# zero_board.net
KiCad netlist of a schematic drawn in EAGLE
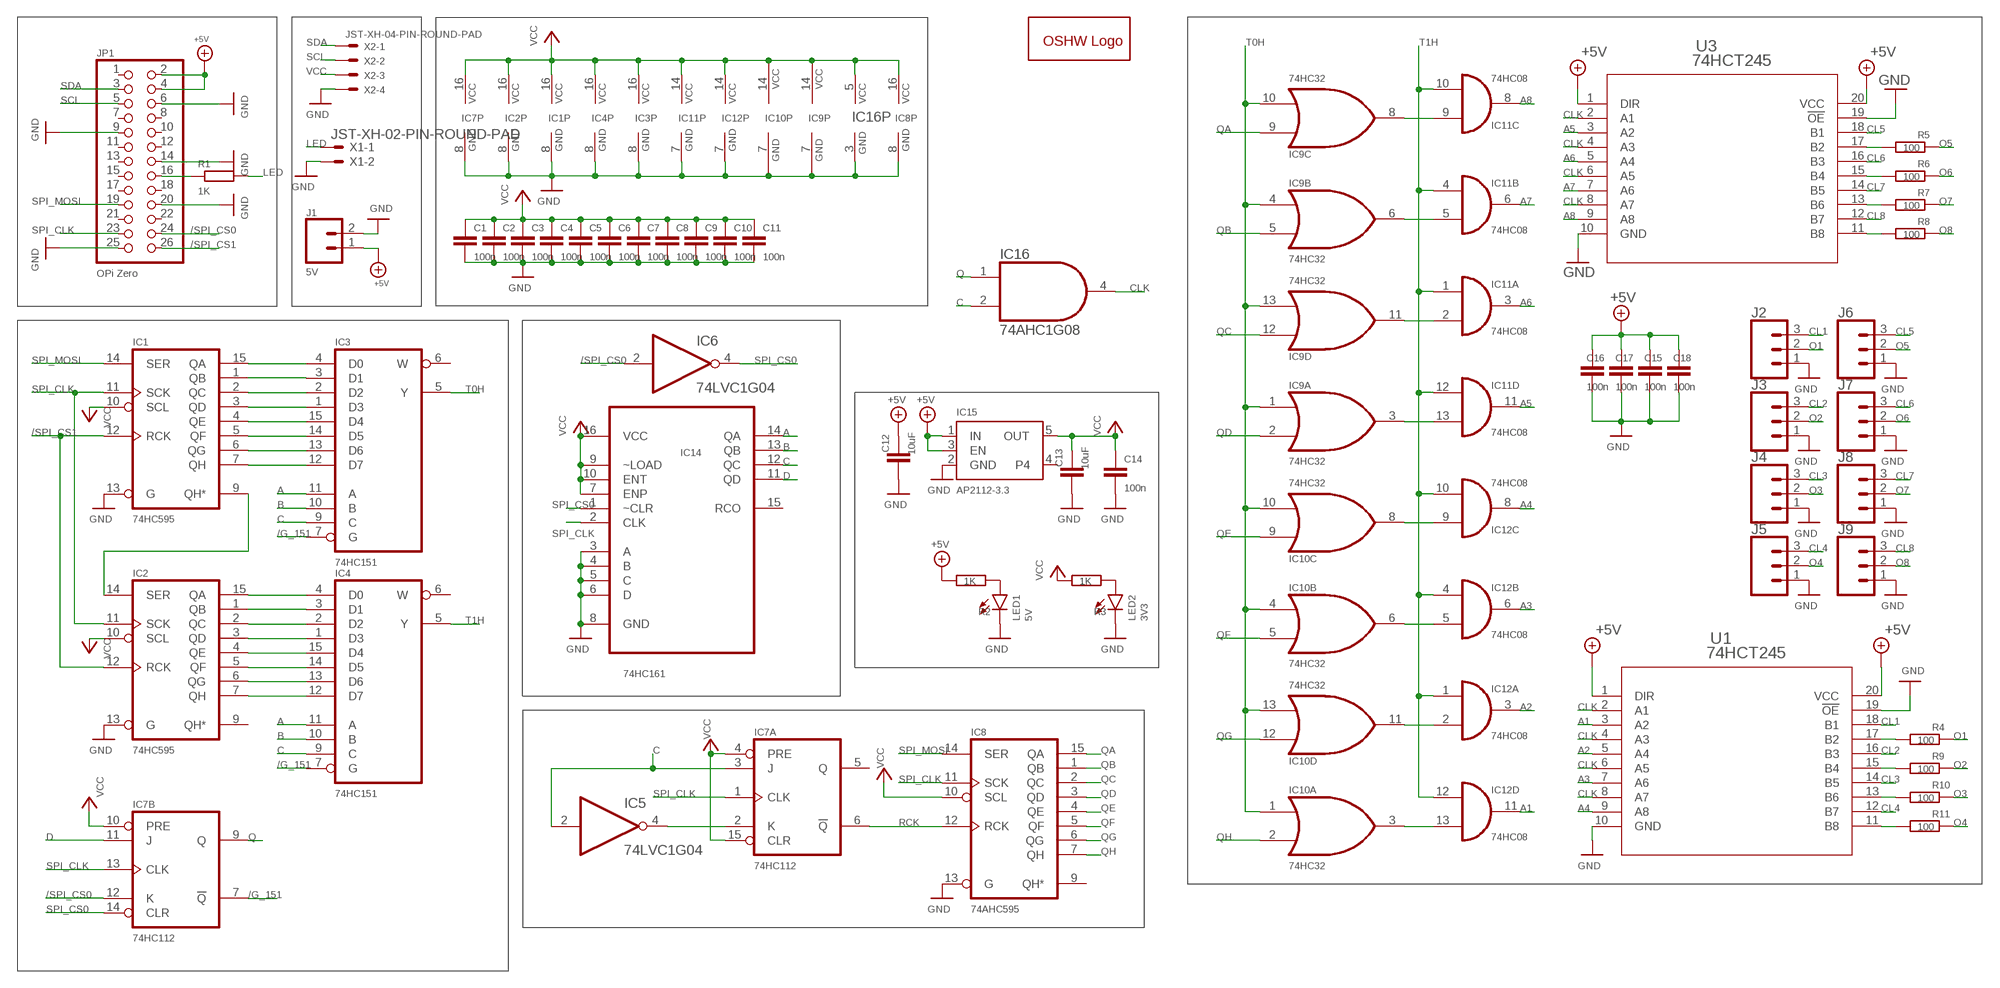
[diagram p0: schematic, sheet 1]

(export (version "E")
  (design (tool "Eeschema 10.0.6"))
  (components
    (comp (ref "C1")
      (value "100n")
      (footprint "eagle-import:C0603")
      (libsource (lib "eagle-import") (part "C-EUC0603"))
    )
    (comp (ref "C2")
      (value "100n")
      (footprint "eagle-import:C0603")
      (libsource (lib "eagle-import") (part "C-EUC0603"))
    )
    (comp (ref "C3")
      (value "100n")
      (footprint "eagle-import:C0603")
      (libsource (lib "eagle-import") (part "C-EUC0603"))
    )
    (comp (ref "C4")
      (value "100n")
      (footprint "eagle-import:C0603")
      (libsource (lib "eagle-import") (part "C-EUC0603"))
    )
    (comp (ref "C5")
      (value "100n")
      (footprint "eagle-import:C0603")
      (libsource (lib "eagle-import") (part "C-EUC0603"))
    )
    (comp (ref "C6")
      (value "100n")
      (footprint "eagle-import:C0603")
      (libsource (lib "eagle-import") (part "C-EUC0603"))
    )
    (comp (ref "C7")
      (value "100n")
      (footprint "eagle-import:C0603")
      (libsource (lib "eagle-import") (part "C-EUC0603"))
    )
    (comp (ref "C8")
      (value "100n")
      (footprint "eagle-import:C0603")
      (libsource (lib "eagle-import") (part "C-EUC0603"))
    )
    (comp (ref "C9")
      (value "100n")
      (footprint "eagle-import:C0603")
      (libsource (lib "eagle-import") (part "C-EUC0603"))
    )
    (comp (ref "C10")
      (value "100n")
      (footprint "eagle-import:C0603")
      (libsource (lib "eagle-import") (part "C-EUC0603"))
    )
    (comp (ref "C11")
      (value "100n")
      (footprint "eagle-import:C0603")
      (libsource (lib "eagle-import") (part "C-EUC0603"))
    )
    (comp (ref "C12")
      (value "10uF")
      (footprint "eagle-import:C0805")
      (libsource (lib "eagle-import") (part "C-EUC0805"))
    )
    (comp (ref "C13")
      (value "10uF")
      (footprint "eagle-import:C0805")
      (libsource (lib "eagle-import") (part "C-EUC0805"))
    )
    (comp (ref "C14")
      (value "100n")
      (footprint "eagle-import:C0603")
      (libsource (lib "eagle-import") (part "C-EUC0603"))
    )
    (comp (ref "C15")
      (value "100n")
      (footprint "eagle-import:C0603")
      (libsource (lib "eagle-import") (part "C-EUC0603"))
    )
    (comp (ref "C16")
      (value "100n")
      (footprint "eagle-import:C0603")
      (libsource (lib "eagle-import") (part "C-EUC0603"))
    )
    (comp (ref "C17")
      (value "100n")
      (footprint "eagle-import:C0603")
      (libsource (lib "eagle-import") (part "C-EUC0603"))
    )
    (comp (ref "C18")
      (value "100n")
      (footprint "eagle-import:C0603")
      (libsource (lib "eagle-import") (part "C-EUC0603"))
    )
    (comp (ref "GOLD_ORB_SM1")
      (value "OSHWLOGOLOGO5MM")
      (footprint "eagle-import:OSHW_5MM")
      (libsource (lib "eagle-import") (part "OSHWLOGOLOGO5MM"))
    )
    (comp (ref "IC1")
      (value "74HC595")
      (footprint "eagle-import:SO16")
      (libsource (lib "eagle-import") (part "74595DHC"))
    )
    (comp (ref "IC2")
      (value "74HC595")
      (footprint "eagle-import:SO16")
      (libsource (lib "eagle-import") (part "74595DHC"))
    )
    (comp (ref "IC3")
      (value "74HC151")
      (footprint "eagle-import:SO16")
      (libsource (lib "eagle-import") (part "74151DHC"))
    )
    (comp (ref "IC4")
      (value "74HC151")
      (footprint "eagle-import:SO16")
      (libsource (lib "eagle-import") (part "74151DHC"))
    )
    (comp (ref "IC5")
      (value "74LVC1G04")
      (footprint "eagle-import:SC70-5")
      (libsource (lib "eagle-import") (part "741G04DCKLVC"))
    )
    (comp (ref "IC6")
      (value "74LVC1G04")
      (footprint "eagle-import:SC70-5")
      (libsource (lib "eagle-import") (part "741G04DCKLVC"))
    )
    (comp (ref "IC7")
      (value "74HC112")
      (footprint "eagle-import:SO16")
      (libsource (lib "eagle-import") (part "74112DHC"))
    )
    (comp (ref "IC8")
      (value "74AHC595")
      (footprint "eagle-import:SO16")
      (libsource (lib "eagle-import") (part "74595DHC"))
    )
    (comp (ref "IC9")
      (value "74HC32")
      (footprint "eagle-import:SO14")
      (libsource (lib "eagle-import") (part "7432DLS"))
    )
    (comp (ref "IC10")
      (value "74HC32")
      (footprint "eagle-import:SO14")
      (libsource (lib "eagle-import") (part "7432DLS"))
    )
    (comp (ref "IC11")
      (value "74HC08")
      (footprint "eagle-import:SO14")
      (libsource (lib "eagle-import") (part "7408DHC"))
    )
    (comp (ref "IC12")
      (value "74HC08")
      (footprint "eagle-import:SO14")
      (libsource (lib "eagle-import") (part "7408DHC"))
    )
    (comp (ref "IC14")
      (value "74HC161")
      (footprint "eagle-import:SOIC127P600X175-16N")
      (fields (field (name "MF") "Texas Instruments") (field (name "MP") "SN74HC161DR"))
      (libsource (lib "eagle-import") (part "SN74HC161DR"))
    )
    (comp (ref "IC15")
      (value "AP2112-3.3")
      (footprint "eagle-import:SOT23-5")
      (libsource (lib "eagle-import") (part "VREG_SOT23-5"))
    )
    (comp (ref "IC16")
      (value "74AHC1G08")
      (footprint "eagle-import:SC70-5")
      (libsource (lib "eagle-import") (part "741G08DCKAHC"))
    )
    (comp (ref "J1")
      (value "5V")
      (footprint "eagle-import:SCREWTERMINAL-3.5MM-2")
      (libsource (lib "eagle-import") (part "CONN_023.5MM"))
    )
    (comp (ref "J2")
      (value "CONN_03SCREW-NS")
      (footprint "eagle-import:SCREWTERMINAL-3.5MM-3-NS")
      (libsource (lib "eagle-import") (part "CONN_03SCREW-NS"))
    )
    (comp (ref "J3")
      (value "CONN_03SCREW-NS")
      (footprint "eagle-import:SCREWTERMINAL-3.5MM-3-NS")
      (libsource (lib "eagle-import") (part "CONN_03SCREW-NS"))
    )
    (comp (ref "J4")
      (value "CONN_03SCREW-NS")
      (footprint "eagle-import:SCREWTERMINAL-3.5MM-3-NS")
      (libsource (lib "eagle-import") (part "CONN_03SCREW-NS"))
    )
    (comp (ref "J5")
      (value "CONN_03SCREW-NS")
      (footprint "eagle-import:SCREWTERMINAL-3.5MM-3-NS")
      (libsource (lib "eagle-import") (part "CONN_03SCREW-NS"))
    )
    (comp (ref "J6")
      (value "CONN_03SCREW-NS")
      (footprint "eagle-import:SCREWTERMINAL-3.5MM-3-NS")
      (libsource (lib "eagle-import") (part "CONN_03SCREW-NS"))
    )
    (comp (ref "J7")
      (value "CONN_03SCREW-NS")
      (footprint "eagle-import:SCREWTERMINAL-3.5MM-3-NS")
      (libsource (lib "eagle-import") (part "CONN_03SCREW-NS"))
    )
    (comp (ref "J8")
      (value "CONN_03SCREW-NS")
      (footprint "eagle-import:SCREWTERMINAL-3.5MM-3-NS")
      (libsource (lib "eagle-import") (part "CONN_03SCREW-NS"))
    )
    (comp (ref "J9")
      (value "CONN_03SCREW-NS")
      (footprint "eagle-import:SCREWTERMINAL-3.5MM-3-NS")
      (libsource (lib "eagle-import") (part "CONN_03SCREW-NS"))
    )
    (comp (ref "JP1")
      (value "OPi Zero")
      (footprint "eagle-import:2X13")
      (libsource (lib "eagle-import") (part "PINHD-2X13"))
    )
    (comp (ref "LED1")
      (value "5V")
      (footprint "eagle-import:CHIP-LED0603")
      (libsource (lib "eagle-import") (part "LEDCHIP-LED0603"))
    )
    (comp (ref "LED2")
      (value "3V3")
      (footprint "eagle-import:CHIP-LED0603")
      (libsource (lib "eagle-import") (part "LEDCHIP-LED0603"))
    )
    (comp (ref "R1")
      (value "1K")
      (footprint "eagle-import:R0603")
      (libsource (lib "eagle-import") (part "R-EU_R0603"))
    )
    (comp (ref "R2")
      (value "1K")
      (footprint "eagle-import:R0603")
      (libsource (lib "eagle-import") (part "R-EU_R0603"))
    )
    (comp (ref "R3")
      (value "1K")
      (footprint "eagle-import:R0603")
      (libsource (lib "eagle-import") (part "R-EU_R0603"))
    )
    (comp (ref "R4")
      (value "100")
      (footprint "eagle-import:R0603")
      (libsource (lib "eagle-import") (part "R-EU_R0603"))
    )
    (comp (ref "R5")
      (value "100")
      (footprint "eagle-import:R0603")
      (libsource (lib "eagle-import") (part "R-EU_R0603"))
    )
    (comp (ref "R6")
      (value "100")
      (footprint "eagle-import:R0603")
      (libsource (lib "eagle-import") (part "R-EU_R0603"))
    )
    (comp (ref "R7")
      (value "100")
      (footprint "eagle-import:R0603")
      (libsource (lib "eagle-import") (part "R-EU_R0603"))
    )
    (comp (ref "R8")
      (value "100")
      (footprint "eagle-import:R0603")
      (libsource (lib "eagle-import") (part "R-EU_R0603"))
    )
    (comp (ref "R9")
      (value "100")
      (footprint "eagle-import:R0603")
      (libsource (lib "eagle-import") (part "R-EU_R0603"))
    )
    (comp (ref "R10")
      (value "100")
      (footprint "eagle-import:R0603")
      (libsource (lib "eagle-import") (part "R-EU_R0603"))
    )
    (comp (ref "R11")
      (value "100")
      (footprint "eagle-import:R0603")
      (libsource (lib "eagle-import") (part "R-EU_R0603"))
    )
    (comp (ref "U1")
      (value "74HCT245")
      (footprint "eagle-import:PW20")
      (fields
        (field (name "GENERIC_PART_NUMBER") "SN74HCT245")
        (field (name "MANUFACTURER") "Texas Instruments")
        (field (name "MANUFACTURER_PART_NUMBER") "SN74HCT245PWR")
      )
      (libsource (lib "eagle-import") (part "SN74HCT245PWR"))
    )
    (comp (ref "U3")
      (value "74HCT245")
      (footprint "eagle-import:PW20")
      (fields
        (field (name "GENERIC_PART_NUMBER") "SN74HCT245")
        (field (name "MANUFACTURER") "Texas Instruments")
        (field (name "MANUFACTURER_PART_NUMBER") "SN74HCT245PWR")
      )
      (libsource (lib "eagle-import") (part "SN74HCT245PWR"))
    )
    (comp (ref "X1")
      (value "JST-XH-02-PIN-ROUND-PAD")
      (footprint "eagle-import:JST-XH-02-PACKAGE-ROUND-PAD")
      (libsource (lib "eagle-import") (part "JST-XH-02-PIN-ROUND-PAD"))
    )
    (comp (ref "X2")
      (value "JST-XH-04-PIN-ROUND-PAD")
      (footprint "eagle-import:JST-XH-04-PACKAGE-ROUND-PAD")
      (libsource (lib "eagle-import") (part "JST-XH-04-PIN-ROUND-PAD"))
    )
  )
  (nets
    (net (code "1") (name "+5V") (class "Default")
      (node (ref "C12") (pin "1") (pinfunction "1_1") (pintype "passive"))
      (node (ref "C15") (pin "1") (pinfunction "1_1") (pintype "passive"))
      (node (ref "C16") (pin "1") (pinfunction "1_1") (pintype "passive"))
      (node (ref "C17") (pin "1") (pinfunction "1_1") (pintype "passive"))
      (node (ref "C18") (pin "1") (pinfunction "1_1") (pintype "passive"))
      (node (ref "IC15") (pin "1") (pinfunction "IN_1") (pintype "power_in"))
      (node (ref "IC15") (pin "3") (pinfunction "EN_3") (pintype "input"))
      (node (ref "J1") (pin "1") (pinfunction "1_1") (pintype "passive"))
      (node (ref "JP1") (pin "2") (pinfunction "2_2") (pintype "passive"))
      (node (ref "JP1") (pin "4") (pinfunction "4_4") (pintype "passive"))
      (node (ref "R2") (pin "1") (pinfunction "1_1") (pintype "passive"))
      (node (ref "U1") (pin "1") (pinfunction "DIR_1") (pintype "input"))
      (node (ref "U1") (pin "20") (pinfunction "VCC_20") (pintype "power_in"))
      (node (ref "U3") (pin "1") (pinfunction "DIR_1") (pintype "input"))
      (node (ref "U3") (pin "20") (pinfunction "VCC_20") (pintype "power_in"))
    )
    (net (code "2") (name "/A") (class "Default")
      (node (ref "IC14") (pin "14") (pinfunction "QA_14") (pintype "output"))
      (node (ref "IC3") (pin "11") (pinfunction "A_11") (pintype "input"))
      (node (ref "IC4") (pin "11") (pinfunction "A_11") (pintype "input"))
    )
    (net (code "3") (name "/A1") (class "Default")
      (node (ref "IC12") (pin "11") (pinfunction "O_11") (pintype "output"))
      (node (ref "U1") (pin "3") (pinfunction "A2_3") (pintype "bidirectional"))
    )
    (net (code "4") (name "/A2") (class "Default")
      (node (ref "IC12") (pin "3") (pinfunction "O_3") (pintype "output"))
      (node (ref "U1") (pin "5") (pinfunction "A4_5") (pintype "bidirectional"))
    )
    (net (code "5") (name "/A3") (class "Default")
      (node (ref "IC12") (pin "6") (pinfunction "O_6") (pintype "output"))
      (node (ref "U1") (pin "7") (pinfunction "A6_7") (pintype "bidirectional"))
    )
    (net (code "6") (name "/A4") (class "Default")
      (node (ref "IC12") (pin "8") (pinfunction "O_8") (pintype "output"))
      (node (ref "U1") (pin "9") (pinfunction "A8_9") (pintype "bidirectional"))
    )
    (net (code "7") (name "/A5") (class "Default")
      (node (ref "IC11") (pin "11") (pinfunction "O_11") (pintype "output"))
      (node (ref "U3") (pin "3") (pinfunction "A2_3") (pintype "bidirectional"))
    )
    (net (code "8") (name "/A6") (class "Default")
      (node (ref "IC11") (pin "3") (pinfunction "O_3") (pintype "output"))
      (node (ref "U3") (pin "5") (pinfunction "A4_5") (pintype "bidirectional"))
    )
    (net (code "9") (name "/A7") (class "Default")
      (node (ref "IC11") (pin "6") (pinfunction "O_6") (pintype "output"))
      (node (ref "U3") (pin "7") (pinfunction "A6_7") (pintype "bidirectional"))
    )
    (net (code "10") (name "/A8") (class "Default")
      (node (ref "IC11") (pin "8") (pinfunction "O_8") (pintype "output"))
      (node (ref "U3") (pin "9") (pinfunction "A8_9") (pintype "bidirectional"))
    )
    (net (code "11") (name "/B") (class "Default")
      (node (ref "IC14") (pin "13") (pinfunction "QB_13") (pintype "output"))
      (node (ref "IC3") (pin "10") (pinfunction "B_10") (pintype "input"))
      (node (ref "IC4") (pin "10") (pinfunction "B_10") (pintype "input"))
    )
    (net (code "12") (name "/C") (class "Default")
      (node (ref "IC14") (pin "12") (pinfunction "QC_12") (pintype "output"))
      (node (ref "IC16") (pin "2") (pinfunction "I1_2") (pintype "input"))
      (node (ref "IC3") (pin "9") (pinfunction "C_9") (pintype "input"))
      (node (ref "IC4") (pin "9") (pinfunction "C_9") (pintype "input"))
      (node (ref "IC5") (pin "2") (pinfunction "I_2") (pintype "input"))
      (node (ref "IC7") (pin "3") (pinfunction "J_3") (pintype "input"))
    )
    (net (code "13") (name "/CL1") (class "Default")
      (node (ref "J2") (pin "3") (pinfunction "3_3") (pintype "passive"))
      (node (ref "U1") (pin "18") (pinfunction "B1_18") (pintype "bidirectional"))
    )
    (net (code "14") (name "/CL2") (class "Default")
      (node (ref "J3") (pin "3") (pinfunction "3_3") (pintype "passive"))
      (node (ref "U1") (pin "16") (pinfunction "B3_16") (pintype "bidirectional"))
    )
    (net (code "15") (name "/CL3") (class "Default")
      (node (ref "J4") (pin "3") (pinfunction "3_3") (pintype "passive"))
      (node (ref "U1") (pin "14") (pinfunction "B5_14") (pintype "bidirectional"))
    )
    (net (code "16") (name "/CL4") (class "Default")
      (node (ref "J5") (pin "3") (pinfunction "3_3") (pintype "passive"))
      (node (ref "U1") (pin "12") (pinfunction "B7_12") (pintype "bidirectional"))
    )
    (net (code "17") (name "/CL5") (class "Default")
      (node (ref "J6") (pin "3") (pinfunction "3_3") (pintype "passive"))
      (node (ref "U3") (pin "18") (pinfunction "B1_18") (pintype "bidirectional"))
    )
    (net (code "18") (name "/CL6") (class "Default")
      (node (ref "J7") (pin "3") (pinfunction "3_3") (pintype "passive"))
      (node (ref "U3") (pin "16") (pinfunction "B3_16") (pintype "bidirectional"))
    )
    (net (code "19") (name "/CL7") (class "Default")
      (node (ref "J8") (pin "3") (pinfunction "3_3") (pintype "passive"))
      (node (ref "U3") (pin "14") (pinfunction "B5_14") (pintype "bidirectional"))
    )
    (net (code "20") (name "/CL8") (class "Default")
      (node (ref "J9") (pin "3") (pinfunction "3_3") (pintype "passive"))
      (node (ref "U3") (pin "12") (pinfunction "B7_12") (pintype "bidirectional"))
    )
    (net (code "21") (name "/CLK") (class "Default")
      (node (ref "IC16") (pin "4") (pinfunction "O_4") (pintype "output"))
      (node (ref "U1") (pin "2") (pinfunction "A1_2") (pintype "bidirectional"))
      (node (ref "U1") (pin "4") (pinfunction "A3_4") (pintype "bidirectional"))
      (node (ref "U1") (pin "6") (pinfunction "A5_6") (pintype "bidirectional"))
      (node (ref "U1") (pin "8") (pinfunction "A7_8") (pintype "bidirectional"))
      (node (ref "U3") (pin "2") (pinfunction "A1_2") (pintype "bidirectional"))
      (node (ref "U3") (pin "4") (pinfunction "A3_4") (pintype "bidirectional"))
      (node (ref "U3") (pin "6") (pinfunction "A5_6") (pintype "bidirectional"))
      (node (ref "U3") (pin "8") (pinfunction "A7_8") (pintype "bidirectional"))
    )
    (net (code "22") (name "/D") (class "Default")
      (node (ref "IC14") (pin "11") (pinfunction "QD_11") (pintype "output"))
      (node (ref "IC7") (pin "11") (pinfunction "J_11") (pintype "input"))
    )
    (net (code "23") (name "/LED") (class "Default")
      (node (ref "R1") (pin "2") (pinfunction "2_2") (pintype "passive"))
      (node (ref "X1") (pin "1") (pinfunction "S_1") (pintype "passive"))
    )
    (net (code "24") (name "/O1") (class "Default")
      (node (ref "J2") (pin "2") (pinfunction "2_2") (pintype "passive"))
      (node (ref "R4") (pin "2") (pinfunction "2_2") (pintype "passive"))
    )
    (net (code "25") (name "/O2") (class "Default")
      (node (ref "J3") (pin "2") (pinfunction "2_2") (pintype "passive"))
      (node (ref "R9") (pin "2") (pinfunction "2_2") (pintype "passive"))
    )
    (net (code "26") (name "/O3") (class "Default")
      (node (ref "J4") (pin "2") (pinfunction "2_2") (pintype "passive"))
      (node (ref "R10") (pin "2") (pinfunction "2_2") (pintype "passive"))
    )
    (net (code "27") (name "/O4") (class "Default")
      (node (ref "J5") (pin "2") (pinfunction "2_2") (pintype "passive"))
      (node (ref "R11") (pin "2") (pinfunction "2_2") (pintype "passive"))
    )
    (net (code "28") (name "/O5") (class "Default")
      (node (ref "J6") (pin "2") (pinfunction "2_2") (pintype "passive"))
      (node (ref "R5") (pin "2") (pinfunction "2_2") (pintype "passive"))
    )
    (net (code "29") (name "/O6") (class "Default")
      (node (ref "J7") (pin "2") (pinfunction "2_2") (pintype "passive"))
      (node (ref "R6") (pin "2") (pinfunction "2_2") (pintype "passive"))
    )
    (net (code "30") (name "/O7") (class "Default")
      (node (ref "J8") (pin "2") (pinfunction "2_2") (pintype "passive"))
      (node (ref "R7") (pin "2") (pinfunction "2_2") (pintype "passive"))
    )
    (net (code "31") (name "/O8") (class "Default")
      (node (ref "J9") (pin "2") (pinfunction "2_2") (pintype "passive"))
      (node (ref "R8") (pin "2") (pinfunction "2_2") (pintype "passive"))
    )
    (net (code "32") (name "/Q") (class "Default")
      (node (ref "IC16") (pin "1") (pinfunction "I0_1") (pintype "input"))
      (node (ref "IC7") (pin "9") (pinfunction "Q_9") (pintype "output"))
    )
    (net (code "33") (name "/QA") (class "Default")
      (node (ref "IC8") (pin "15") (pinfunction "QA_15") (pintype "tri_state"))
      (node (ref "IC9") (pin "9") (pinfunction "I0_9") (pintype "input"))
    )
    (net (code "34") (name "/QB") (class "Default")
      (node (ref "IC8") (pin "1") (pinfunction "QB_1") (pintype "tri_state"))
      (node (ref "IC9") (pin "5") (pinfunction "I1_5") (pintype "input"))
    )
    (net (code "35") (name "/QC") (class "Default")
      (node (ref "IC8") (pin "2") (pinfunction "QC_2") (pintype "tri_state"))
      (node (ref "IC9") (pin "12") (pinfunction "I0_12") (pintype "input"))
    )
    (net (code "36") (name "/QD") (class "Default")
      (node (ref "IC8") (pin "3") (pinfunction "QD_3") (pintype "tri_state"))
      (node (ref "IC9") (pin "2") (pinfunction "I1_2") (pintype "input"))
    )
    (net (code "37") (name "/QE") (class "Default")
      (node (ref "IC10") (pin "9") (pinfunction "I0_9") (pintype "input"))
      (node (ref "IC8") (pin "4") (pinfunction "QE_4") (pintype "tri_state"))
    )
    (net (code "38") (name "/QF") (class "Default")
      (node (ref "IC10") (pin "5") (pinfunction "I1_5") (pintype "input"))
      (node (ref "IC8") (pin "5") (pinfunction "QF_5") (pintype "tri_state"))
    )
    (net (code "39") (name "/QG") (class "Default")
      (node (ref "IC10") (pin "12") (pinfunction "I0_12") (pintype "input"))
      (node (ref "IC8") (pin "6") (pinfunction "QG_6") (pintype "tri_state"))
    )
    (net (code "40") (name "/QH") (class "Default")
      (node (ref "IC10") (pin "2") (pinfunction "I1_2") (pintype "input"))
      (node (ref "IC8") (pin "7") (pinfunction "QH_7") (pintype "tri_state"))
    )
    (net (code "41") (name "/RCK") (class "Default")
      (node (ref "IC7") (pin "6") (pinfunction "~{Q}_6") (pintype "output"))
      (node (ref "IC8") (pin "12") (pinfunction "RCK_12") (pintype "input"))
    )
    (net (code "42") (name "/SCL") (class "Default")
      (node (ref "JP1") (pin "5") (pinfunction "5_5") (pintype "passive"))
      (node (ref "X2") (pin "2") (pinfunction "S_2") (pintype "passive"))
    )
    (net (code "43") (name "/SDA") (class "Default")
      (node (ref "JP1") (pin "3") (pinfunction "3_3") (pintype "passive"))
      (node (ref "X2") (pin "1") (pinfunction "S_1") (pintype "passive"))
    )
    (net (code "44") (name "/SPI_CLK") (class "Default")
      (node (ref "IC1") (pin "11") (pinfunction "SCK_11") (pintype "input"))
      (node (ref "IC14") (pin "2") (pinfunction "CLK_2") (pintype "input"))
      (node (ref "IC2") (pin "11") (pinfunction "SCK_11") (pintype "input"))
      (node (ref "IC7") (pin "1") (pinfunction "CLK_1") (pintype "input"))
      (node (ref "IC7") (pin "13") (pinfunction "CLK_13") (pintype "input"))
      (node (ref "IC8") (pin "11") (pinfunction "SCK_11") (pintype "input"))
      (node (ref "JP1") (pin "23") (pinfunction "23_23") (pintype "passive"))
    )
    (net (code "45") (name "/SPI_CS0") (class "Default")
      (node (ref "IC14") (pin "1") (pinfunction "~{CLR}_1") (pintype "input"))
      (node (ref "IC6") (pin "4") (pinfunction "O_4") (pintype "output"))
      (node (ref "IC7") (pin "14") (pinfunction "CLR_14") (pintype "input"))
    )
    (net (code "46") (name "/SPI_MOSI") (class "Default")
      (node (ref "IC1") (pin "14") (pinfunction "SER_14") (pintype "input"))
      (node (ref "IC8") (pin "14") (pinfunction "SER_14") (pintype "input"))
      (node (ref "JP1") (pin "19") (pinfunction "19_19") (pintype "passive"))
    )
    (net (code "47") (name "/T0H") (class "Default")
      (node (ref "IC10") (pin "1") (pinfunction "I0_1") (pintype "input"))
      (node (ref "IC10") (pin "10") (pinfunction "I1_10") (pintype "input"))
      (node (ref "IC10") (pin "13") (pinfunction "I1_13") (pintype "input"))
      (node (ref "IC10") (pin "4") (pinfunction "I0_4") (pintype "input"))
      (node (ref "IC3") (pin "5") (pinfunction "Y_5") (pintype "output"))
      (node (ref "IC9") (pin "1") (pinfunction "I0_1") (pintype "input"))
      (node (ref "IC9") (pin "10") (pinfunction "I1_10") (pintype "input"))
      (node (ref "IC9") (pin "13") (pinfunction "I1_13") (pintype "input"))
      (node (ref "IC9") (pin "4") (pinfunction "I0_4") (pintype "input"))
    )
    (net (code "48") (name "/T1H") (class "Default")
      (node (ref "IC11") (pin "1") (pinfunction "I0_1") (pintype "input"))
      (node (ref "IC11") (pin "10") (pinfunction "I1_10") (pintype "input"))
      (node (ref "IC11") (pin "12") (pinfunction "I0_12") (pintype "input"))
      (node (ref "IC11") (pin "4") (pinfunction "I0_4") (pintype "input"))
      (node (ref "IC12") (pin "1") (pinfunction "I0_1") (pintype "input"))
      (node (ref "IC12") (pin "10") (pinfunction "I1_10") (pintype "input"))
      (node (ref "IC12") (pin "12") (pinfunction "I0_12") (pintype "input"))
      (node (ref "IC12") (pin "4") (pinfunction "I0_4") (pintype "input"))
      (node (ref "IC4") (pin "5") (pinfunction "Y_5") (pintype "output"))
    )
    (net (code "49") (name "/{slash}G_151") (class "Default")
      (node (ref "IC3") (pin "7") (pinfunction "G_7") (pintype "input"))
      (node (ref "IC4") (pin "7") (pinfunction "G_7") (pintype "input"))
      (node (ref "IC7") (pin "7") (pinfunction "~{Q}_7") (pintype "output"))
    )
    (net (code "50") (name "/{slash}SPI_CS0") (class "Default")
      (node (ref "IC6") (pin "2") (pinfunction "I_2") (pintype "input"))
      (node (ref "IC7") (pin "12") (pinfunction "K_12") (pintype "input"))
      (node (ref "JP1") (pin "24") (pinfunction "24_24") (pintype "passive"))
    )
    (net (code "51") (name "/{slash}SPI_CS1") (class "Default")
      (node (ref "IC1") (pin "12") (pinfunction "RCK_12") (pintype "input"))
      (node (ref "IC2") (pin "12") (pinfunction "RCK_12") (pintype "input"))
      (node (ref "JP1") (pin "26") (pinfunction "26_26") (pintype "passive"))
    )
    (net (code "52") (name "GND") (class "Default")
      (node (ref "C1") (pin "2") (pinfunction "2_2") (pintype "passive"))
      (node (ref "C10") (pin "2") (pinfunction "2_2") (pintype "passive"))
      (node (ref "C11") (pin "2") (pinfunction "2_2") (pintype "passive"))
      (node (ref "C12") (pin "2") (pinfunction "2_2") (pintype "passive"))
      (node (ref "C13") (pin "2") (pinfunction "2_2") (pintype "passive"))
      (node (ref "C14") (pin "2") (pinfunction "2_2") (pintype "passive"))
      (node (ref "C15") (pin "2") (pinfunction "2_2") (pintype "passive"))
      (node (ref "C16") (pin "2") (pinfunction "2_2") (pintype "passive"))
      (node (ref "C17") (pin "2") (pinfunction "2_2") (pintype "passive"))
      (node (ref "C18") (pin "2") (pinfunction "2_2") (pintype "passive"))
      (node (ref "C2") (pin "2") (pinfunction "2_2") (pintype "passive"))
      (node (ref "C3") (pin "2") (pinfunction "2_2") (pintype "passive"))
      (node (ref "C4") (pin "2") (pinfunction "2_2") (pintype "passive"))
      (node (ref "C5") (pin "2") (pinfunction "2_2") (pintype "passive"))
      (node (ref "C6") (pin "2") (pinfunction "2_2") (pintype "passive"))
      (node (ref "C7") (pin "2") (pinfunction "2_2") (pintype "passive"))
      (node (ref "C8") (pin "2") (pinfunction "2_2") (pintype "passive"))
      (node (ref "C9") (pin "2") (pinfunction "2_2") (pintype "passive"))
      (node (ref "IC1") (pin "13") (pinfunction "G_13") (pintype "input"))
      (node (ref "IC1") (pin "8") (pinfunction "GND_8") (pintype "power_in"))
      (node (ref "IC10") (pin "7") (pinfunction "GND_7") (pintype "power_in"))
      (node (ref "IC11") (pin "7") (pinfunction "GND_7") (pintype "power_in"))
      (node (ref "IC12") (pin "7") (pinfunction "GND_7") (pintype "power_in"))
      (node (ref "IC14") (pin "3") (pinfunction "A_3") (pintype "input"))
      (node (ref "IC14") (pin "4") (pinfunction "B_4") (pintype "input"))
      (node (ref "IC14") (pin "5") (pinfunction "C_5") (pintype "input"))
      (node (ref "IC14") (pin "6") (pinfunction "D_6") (pintype "input"))
      (node (ref "IC14") (pin "8") (pinfunction "GND_8") (pintype "passive"))
      (node (ref "IC15") (pin "2") (pinfunction "GND_2") (pintype "power_in"))
      (node (ref "IC16") (pin "3") (pinfunction "GND_3") (pintype "power_in"))
      (node (ref "IC2") (pin "13") (pinfunction "G_13") (pintype "input"))
      (node (ref "IC2") (pin "8") (pinfunction "GND_8") (pintype "power_in"))
      (node (ref "IC3") (pin "8") (pinfunction "GND_8") (pintype "power_in"))
      (node (ref "IC4") (pin "8") (pinfunction "GND_8") (pintype "power_in"))
      (node (ref "IC7") (pin "8") (pinfunction "GND_8") (pintype "power_in"))
      (node (ref "IC8") (pin "13") (pinfunction "G_13") (pintype "input"))
      (node (ref "IC8") (pin "8") (pinfunction "GND_8") (pintype "power_in"))
      (node (ref "IC9") (pin "7") (pinfunction "GND_7") (pintype "power_in"))
      (node (ref "J1") (pin "2") (pinfunction "2_2") (pintype "passive"))
      (node (ref "J2") (pin "1") (pinfunction "1_1") (pintype "passive"))
      (node (ref "J3") (pin "1") (pinfunction "1_1") (pintype "passive"))
      (node (ref "J4") (pin "1") (pinfunction "1_1") (pintype "passive"))
      (node (ref "J5") (pin "1") (pinfunction "1_1") (pintype "passive"))
      (node (ref "J6") (pin "1") (pinfunction "1_1") (pintype "passive"))
      (node (ref "J7") (pin "1") (pinfunction "1_1") (pintype "passive"))
      (node (ref "J8") (pin "1") (pinfunction "1_1") (pintype "passive"))
      (node (ref "J9") (pin "1") (pinfunction "1_1") (pintype "passive"))
      (node (ref "JP1") (pin "14") (pinfunction "14_14") (pintype "passive"))
      (node (ref "JP1") (pin "20") (pinfunction "20_20") (pintype "passive"))
      (node (ref "JP1") (pin "25") (pinfunction "25_25") (pintype "passive"))
      (node (ref "JP1") (pin "6") (pinfunction "6_6") (pintype "passive"))
      (node (ref "JP1") (pin "9") (pinfunction "9_9") (pintype "passive"))
      (node (ref "LED1") (pin "C") (pinfunction "C_C") (pintype "passive"))
      (node (ref "LED2") (pin "C") (pinfunction "C_C") (pintype "passive"))
      (node (ref "U1") (pin "10") (pinfunction "GND_10") (pintype "power_in"))
      (node (ref "U1") (pin "19") (pinfunction "~{OE}_19") (pintype "input"))
      (node (ref "U3") (pin "10") (pinfunction "GND_10") (pintype "power_in"))
      (node (ref "U3") (pin "19") (pinfunction "~{OE}_19") (pintype "input"))
      (node (ref "X1") (pin "2") (pinfunction "S_2") (pintype "passive"))
      (node (ref "X2") (pin "4") (pinfunction "S_4") (pintype "passive"))
    )
    (net (code "53") (name "Net-(IC1A-QA)") (class "Default")
      (node (ref "IC1") (pin "15") (pinfunction "QA_15") (pintype "tri_state"))
      (node (ref "IC3") (pin "4") (pinfunction "D0_4") (pintype "input"))
    )
    (net (code "54") (name "Net-(IC1A-QB)") (class "Default")
      (node (ref "IC1") (pin "1") (pinfunction "QB_1") (pintype "tri_state"))
      (node (ref "IC3") (pin "3") (pinfunction "D1_3") (pintype "input"))
    )
    (net (code "55") (name "Net-(IC1A-QC)") (class "Default")
      (node (ref "IC1") (pin "2") (pinfunction "QC_2") (pintype "tri_state"))
      (node (ref "IC3") (pin "2") (pinfunction "D2_2") (pintype "input"))
    )
    (net (code "56") (name "Net-(IC1A-QD)") (class "Default")
      (node (ref "IC1") (pin "3") (pinfunction "QD_3") (pintype "tri_state"))
      (node (ref "IC3") (pin "1") (pinfunction "D3_1") (pintype "input"))
    )
    (net (code "57") (name "Net-(IC1A-QE)") (class "Default")
      (node (ref "IC1") (pin "4") (pinfunction "QE_4") (pintype "tri_state"))
      (node (ref "IC3") (pin "15") (pinfunction "D4_15") (pintype "input"))
    )
    (net (code "58") (name "Net-(IC1A-QF)") (class "Default")
      (node (ref "IC1") (pin "5") (pinfunction "QF_5") (pintype "tri_state"))
      (node (ref "IC3") (pin "14") (pinfunction "D5_14") (pintype "input"))
    )
    (net (code "59") (name "Net-(IC1A-QG)") (class "Default")
      (node (ref "IC1") (pin "6") (pinfunction "QG_6") (pintype "tri_state"))
      (node (ref "IC3") (pin "13") (pinfunction "D6_13") (pintype "input"))
    )
    (net (code "60") (name "Net-(IC1A-QH)") (class "Default")
      (node (ref "IC1") (pin "7") (pinfunction "QH_7") (pintype "tri_state"))
      (node (ref "IC3") (pin "12") (pinfunction "D7_12") (pintype "input"))
    )
    (net (code "61") (name "Net-(IC1A-QH*)") (class "Default")
      (node (ref "IC1") (pin "9") (pinfunction "QH*_9") (pintype "tri_state"))
      (node (ref "IC2") (pin "14") (pinfunction "SER_14") (pintype "input"))
    )
    (net (code "62") (name "Net-(IC2A-QA)") (class "Default")
      (node (ref "IC2") (pin "15") (pinfunction "QA_15") (pintype "tri_state"))
      (node (ref "IC4") (pin "4") (pinfunction "D0_4") (pintype "input"))
    )
    (net (code "63") (name "Net-(IC2A-QB)") (class "Default")
      (node (ref "IC2") (pin "1") (pinfunction "QB_1") (pintype "tri_state"))
      (node (ref "IC4") (pin "3") (pinfunction "D1_3") (pintype "input"))
    )
    (net (code "64") (name "Net-(IC2A-QC)") (class "Default")
      (node (ref "IC2") (pin "2") (pinfunction "QC_2") (pintype "tri_state"))
      (node (ref "IC4") (pin "2") (pinfunction "D2_2") (pintype "input"))
    )
    (net (code "65") (name "Net-(IC2A-QD)") (class "Default")
      (node (ref "IC2") (pin "3") (pinfunction "QD_3") (pintype "tri_state"))
      (node (ref "IC4") (pin "1") (pinfunction "D3_1") (pintype "input"))
    )
    (net (code "66") (name "Net-(IC2A-QE)") (class "Default")
      (node (ref "IC2") (pin "4") (pinfunction "QE_4") (pintype "tri_state"))
      (node (ref "IC4") (pin "15") (pinfunction "D4_15") (pintype "input"))
    )
    (net (code "67") (name "Net-(IC2A-QF)") (class "Default")
      (node (ref "IC2") (pin "5") (pinfunction "QF_5") (pintype "tri_state"))
      (node (ref "IC4") (pin "14") (pinfunction "D5_14") (pintype "input"))
    )
    (net (code "68") (name "Net-(IC2A-QG)") (class "Default")
      (node (ref "IC2") (pin "6") (pinfunction "QG_6") (pintype "tri_state"))
      (node (ref "IC4") (pin "13") (pinfunction "D6_13") (pintype "input"))
    )
    (net (code "69") (name "Net-(IC2A-QH)") (class "Default")
      (node (ref "IC2") (pin "7") (pinfunction "QH_7") (pintype "tri_state"))
      (node (ref "IC4") (pin "12") (pinfunction "D7_12") (pintype "input"))
    )
    (net (code "70") (name "Net-(IC5A-O)") (class "Default")
      (node (ref "IC5") (pin "4") (pinfunction "O_4") (pintype "output"))
      (node (ref "IC7") (pin "2") (pinfunction "K_2") (pintype "input"))
    )
    (net (code "71") (name "Net-(IC10A-O)") (class "Default")
      (node (ref "IC10") (pin "3") (pinfunction "O_3") (pintype "output"))
      (node (ref "IC12") (pin "13") (pinfunction "I1_13") (pintype "input"))
    )
    (net (code "72") (name "Net-(IC10B-O)") (class "Default")
      (node (ref "IC10") (pin "6") (pinfunction "O_6") (pintype "output"))
      (node (ref "IC12") (pin "5") (pinfunction "I1_5") (pintype "input"))
    )
    (net (code "73") (name "Net-(IC10C-O)") (class "Default")
      (node (ref "IC10") (pin "8") (pinfunction "O_8") (pintype "output"))
      (node (ref "IC12") (pin "9") (pinfunction "I0_9") (pintype "input"))
    )
    (net (code "74") (name "Net-(IC10D-O)") (class "Default")
      (node (ref "IC10") (pin "11") (pinfunction "O_11") (pintype "output"))
      (node (ref "IC12") (pin "2") (pinfunction "I1_2") (pintype "input"))
    )
    (net (code "75") (name "Net-(IC11A-I1)") (class "Default")
      (node (ref "IC11") (pin "2") (pinfunction "I1_2") (pintype "input"))
      (node (ref "IC9") (pin "11") (pinfunction "O_11") (pintype "output"))
    )
    (net (code "76") (name "Net-(IC11B-I1)") (class "Default")
      (node (ref "IC11") (pin "5") (pinfunction "I1_5") (pintype "input"))
      (node (ref "IC9") (pin "6") (pinfunction "O_6") (pintype "output"))
    )
    (net (code "77") (name "Net-(IC11C-I0)") (class "Default")
      (node (ref "IC11") (pin "9") (pinfunction "I0_9") (pintype "input"))
      (node (ref "IC9") (pin "8") (pinfunction "O_8") (pintype "output"))
    )
    (net (code "78") (name "Net-(IC11D-I1)") (class "Default")
      (node (ref "IC11") (pin "13") (pinfunction "I1_13") (pintype "input"))
      (node (ref "IC9") (pin "3") (pinfunction "O_3") (pintype "output"))
    )
    (net (code "79") (name "Net-(JP1-Pad16)") (class "Default")
      (node (ref "JP1") (pin "16") (pinfunction "16_16") (pintype "passive"))
      (node (ref "R1") (pin "1") (pinfunction "1_1") (pintype "passive"))
    )
    (net (code "80") (name "Net-(LED1-PadA)") (class "Default")
      (node (ref "LED1") (pin "A") (pinfunction "A_A") (pintype "passive"))
      (node (ref "R2") (pin "2") (pinfunction "2_2") (pintype "passive"))
    )
    (net (code "81") (name "Net-(LED2-PadA)") (class "Default")
      (node (ref "LED2") (pin "A") (pinfunction "A_A") (pintype "passive"))
      (node (ref "R3") (pin "2") (pinfunction "2_2") (pintype "passive"))
    )
    (net (code "82") (name "Net-(U1-B2)") (class "Default")
      (node (ref "R4") (pin "1") (pinfunction "1_1") (pintype "passive"))
      (node (ref "U1") (pin "17") (pinfunction "B2_17") (pintype "bidirectional"))
    )
    (net (code "83") (name "Net-(U1-B4)") (class "Default")
      (node (ref "R9") (pin "1") (pinfunction "1_1") (pintype "passive"))
      (node (ref "U1") (pin "15") (pinfunction "B4_15") (pintype "bidirectional"))
    )
    (net (code "84") (name "Net-(U1-B6)") (class "Default")
      (node (ref "R10") (pin "1") (pinfunction "1_1") (pintype "passive"))
      (node (ref "U1") (pin "13") (pinfunction "B6_13") (pintype "bidirectional"))
    )
    (net (code "85") (name "Net-(U1-B8)") (class "Default")
      (node (ref "R11") (pin "1") (pinfunction "1_1") (pintype "passive"))
      (node (ref "U1") (pin "11") (pinfunction "B8_11") (pintype "bidirectional"))
    )
    (net (code "86") (name "Net-(U3-B2)") (class "Default")
      (node (ref "R5") (pin "1") (pinfunction "1_1") (pintype "passive"))
      (node (ref "U3") (pin "17") (pinfunction "B2_17") (pintype "bidirectional"))
    )
    (net (code "87") (name "Net-(U3-B4)") (class "Default")
      (node (ref "R6") (pin "1") (pinfunction "1_1") (pintype "passive"))
      (node (ref "U3") (pin "15") (pinfunction "B4_15") (pintype "bidirectional"))
    )
    (net (code "88") (name "Net-(U3-B6)") (class "Default")
      (node (ref "R7") (pin "1") (pinfunction "1_1") (pintype "passive"))
      (node (ref "U3") (pin "13") (pinfunction "B6_13") (pintype "bidirectional"))
    )
    (net (code "89") (name "Net-(U3-B8)") (class "Default")
      (node (ref "R8") (pin "1") (pinfunction "1_1") (pintype "passive"))
      (node (ref "U3") (pin "11") (pinfunction "B8_11") (pintype "bidirectional"))
    )
    (net (code "90") (name "VCC") (class "Default")
      (node (ref "C1") (pin "1") (pinfunction "1_1") (pintype "passive"))
      (node (ref "C10") (pin "1") (pinfunction "1_1") (pintype "passive"))
      (node (ref "C11") (pin "1") (pinfunction "1_1") (pintype "passive"))
      (node (ref "C13") (pin "1") (pinfunction "1_1") (pintype "passive"))
      (node (ref "C14") (pin "1") (pinfunction "1_1") (pintype "passive"))
      (node (ref "C2") (pin "1") (pinfunction "1_1") (pintype "passive"))
      (node (ref "C3") (pin "1") (pinfunction "1_1") (pintype "passive"))
      (node (ref "C4") (pin "1") (pinfunction "1_1") (pintype "passive"))
      (node (ref "C5") (pin "1") (pinfunction "1_1") (pintype "passive"))
      (node (ref "C6") (pin "1") (pinfunction "1_1") (pintype "passive"))
      (node (ref "C7") (pin "1") (pinfunction "1_1") (pintype "passive"))
      (node (ref "C8") (pin "1") (pinfunction "1_1") (pintype "passive"))
      (node (ref "C9") (pin "1") (pinfunction "1_1") (pintype "passive"))
      (node (ref "IC1") (pin "10") (pinfunction "SCL_10") (pintype "input"))
      (node (ref "IC1") (pin "16") (pinfunction "VCC_16") (pintype "power_in"))
      (node (ref "IC10") (pin "14") (pinfunction "VCC_14") (pintype "power_in"))
      (node (ref "IC11") (pin "14") (pinfunction "VCC_14") (pintype "power_in"))
      (node (ref "IC12") (pin "14") (pinfunction "VCC_14") (pintype "power_in"))
      (node (ref "IC14") (pin "10") (pinfunction "ENT_10") (pintype "input"))
      (node (ref "IC14") (pin "16") (pinfunction "VCC_16") (pintype "power_in"))
      (node (ref "IC14") (pin "7") (pinfunction "ENP_7") (pintype "input"))
      (node (ref "IC14") (pin "9") (pinfunction "~{LOAD}_9") (pintype "input"))
      (node (ref "IC15") (pin "5") (pinfunction "OUT_5") (pintype "power_in"))
      (node (ref "IC16") (pin "5") (pinfunction "VCC_5") (pintype "power_in"))
      (node (ref "IC2") (pin "10") (pinfunction "SCL_10") (pintype "input"))
      (node (ref "IC2") (pin "16") (pinfunction "VCC_16") (pintype "power_in"))
      (node (ref "IC3") (pin "16") (pinfunction "VCC_16") (pintype "power_in"))
      (node (ref "IC4") (pin "16") (pinfunction "VCC_16") (pintype "power_in"))
      (node (ref "IC7") (pin "10") (pinfunction "PRE_10") (pintype "input"))
      (node (ref "IC7") (pin "15") (pinfunction "CLR_15") (pintype "input"))
      (node (ref "IC7") (pin "16") (pinfunction "VCC_16") (pintype "power_in"))
      (node (ref "IC7") (pin "4") (pinfunction "PRE_4") (pintype "input"))
      (node (ref "IC8") (pin "10") (pinfunction "SCL_10") (pintype "input"))
      (node (ref "IC8") (pin "16") (pinfunction "VCC_16") (pintype "power_in"))
      (node (ref "IC9") (pin "14") (pinfunction "VCC_14") (pintype "power_in"))
      (node (ref "R3") (pin "1") (pinfunction "1_1") (pintype "passive"))
      (node (ref "X2") (pin "3") (pinfunction "S_3") (pintype "passive"))
    )
    (net (code "91") (name "unconnected-(IC2A-QH*-Pad9)") (class "Default")
      (node (ref "IC2") (pin "9") (pinfunction "QH*_9") (pintype "tri_state"))
    )
    (net (code "92") (name "unconnected-(IC3A-W-Pad6)") (class "Default")
      (node (ref "IC3") (pin "6") (pinfunction "W_6") (pintype "output"))
    )
    (net (code "93") (name "unconnected-(IC4A-W-Pad6)") (class "Default")
      (node (ref "IC4") (pin "6") (pinfunction "W_6") (pintype "output"))
    )
    (net (code "94") (name "unconnected-(IC7A-Q-Pad5)") (class "Default")
      (node (ref "IC7") (pin "5") (pinfunction "Q_5") (pintype "output"))
    )
    (net (code "95") (name "unconnected-(IC8A-QH*-Pad9)") (class "Default")
      (node (ref "IC8") (pin "9") (pinfunction "QH*_9") (pintype "tri_state"))
    )
    (net (code "96") (name "unconnected-(IC14-RCO-Pad15)") (class "Default")
      (node (ref "IC14") (pin "15") (pinfunction "RCO_15") (pintype "output"))
    )
    (net (code "97") (name "unconnected-(IC15-P4-Pad4)") (class "Default")
      (node (ref "IC15") (pin "4") (pinfunction "P4_4") (pintype "bidirectional"))
    )
    (net (code "98") (name "unconnected-(JP1-Pad1)") (class "Default")
      (node (ref "JP1") (pin "1") (pinfunction "1_1") (pintype "passive"))
    )
    (net (code "99") (name "unconnected-(JP1-Pad7)") (class "Default")
      (node (ref "JP1") (pin "7") (pinfunction "7_7") (pintype "passive"))
    )
    (net (code "100") (name "unconnected-(JP1-Pad8)") (class "Default")
      (node (ref "JP1") (pin "8") (pinfunction "8_8") (pintype "passive"))
    )
    (net (code "101") (name "unconnected-(JP1-Pad10)") (class "Default")
      (node (ref "JP1") (pin "10") (pinfunction "10_10") (pintype "passive"))
    )
    (net (code "102") (name "unconnected-(JP1-Pad11)") (class "Default")
      (node (ref "JP1") (pin "11") (pinfunction "11_11") (pintype "passive"))
    )
    (net (code "103") (name "unconnected-(JP1-Pad12)") (class "Default")
      (node (ref "JP1") (pin "12") (pinfunction "12_12") (pintype "passive"))
    )
    (net (code "104") (name "unconnected-(JP1-Pad13)") (class "Default")
      (node (ref "JP1") (pin "13") (pinfunction "13_13") (pintype "passive"))
    )
    (net (code "105") (name "unconnected-(JP1-Pad15)") (class "Default")
      (node (ref "JP1") (pin "15") (pinfunction "15_15") (pintype "passive"))
    )
    (net (code "106") (name "unconnected-(JP1-Pad17)") (class "Default")
      (node (ref "JP1") (pin "17") (pinfunction "17_17") (pintype "passive"))
    )
    (net (code "107") (name "unconnected-(JP1-Pad18)") (class "Default")
      (node (ref "JP1") (pin "18") (pinfunction "18_18") (pintype "passive"))
    )
    (net (code "108") (name "unconnected-(JP1-Pad21)") (class "Default")
      (node (ref "JP1") (pin "21") (pinfunction "21_21") (pintype "passive"))
    )
    (net (code "109") (name "unconnected-(JP1-Pad22)") (class "Default")
      (node (ref "JP1") (pin "22") (pinfunction "22_22") (pintype "passive"))
    )
  )
)
